# taad.net
KiCad netlist of a schematic drawn in EAGLE
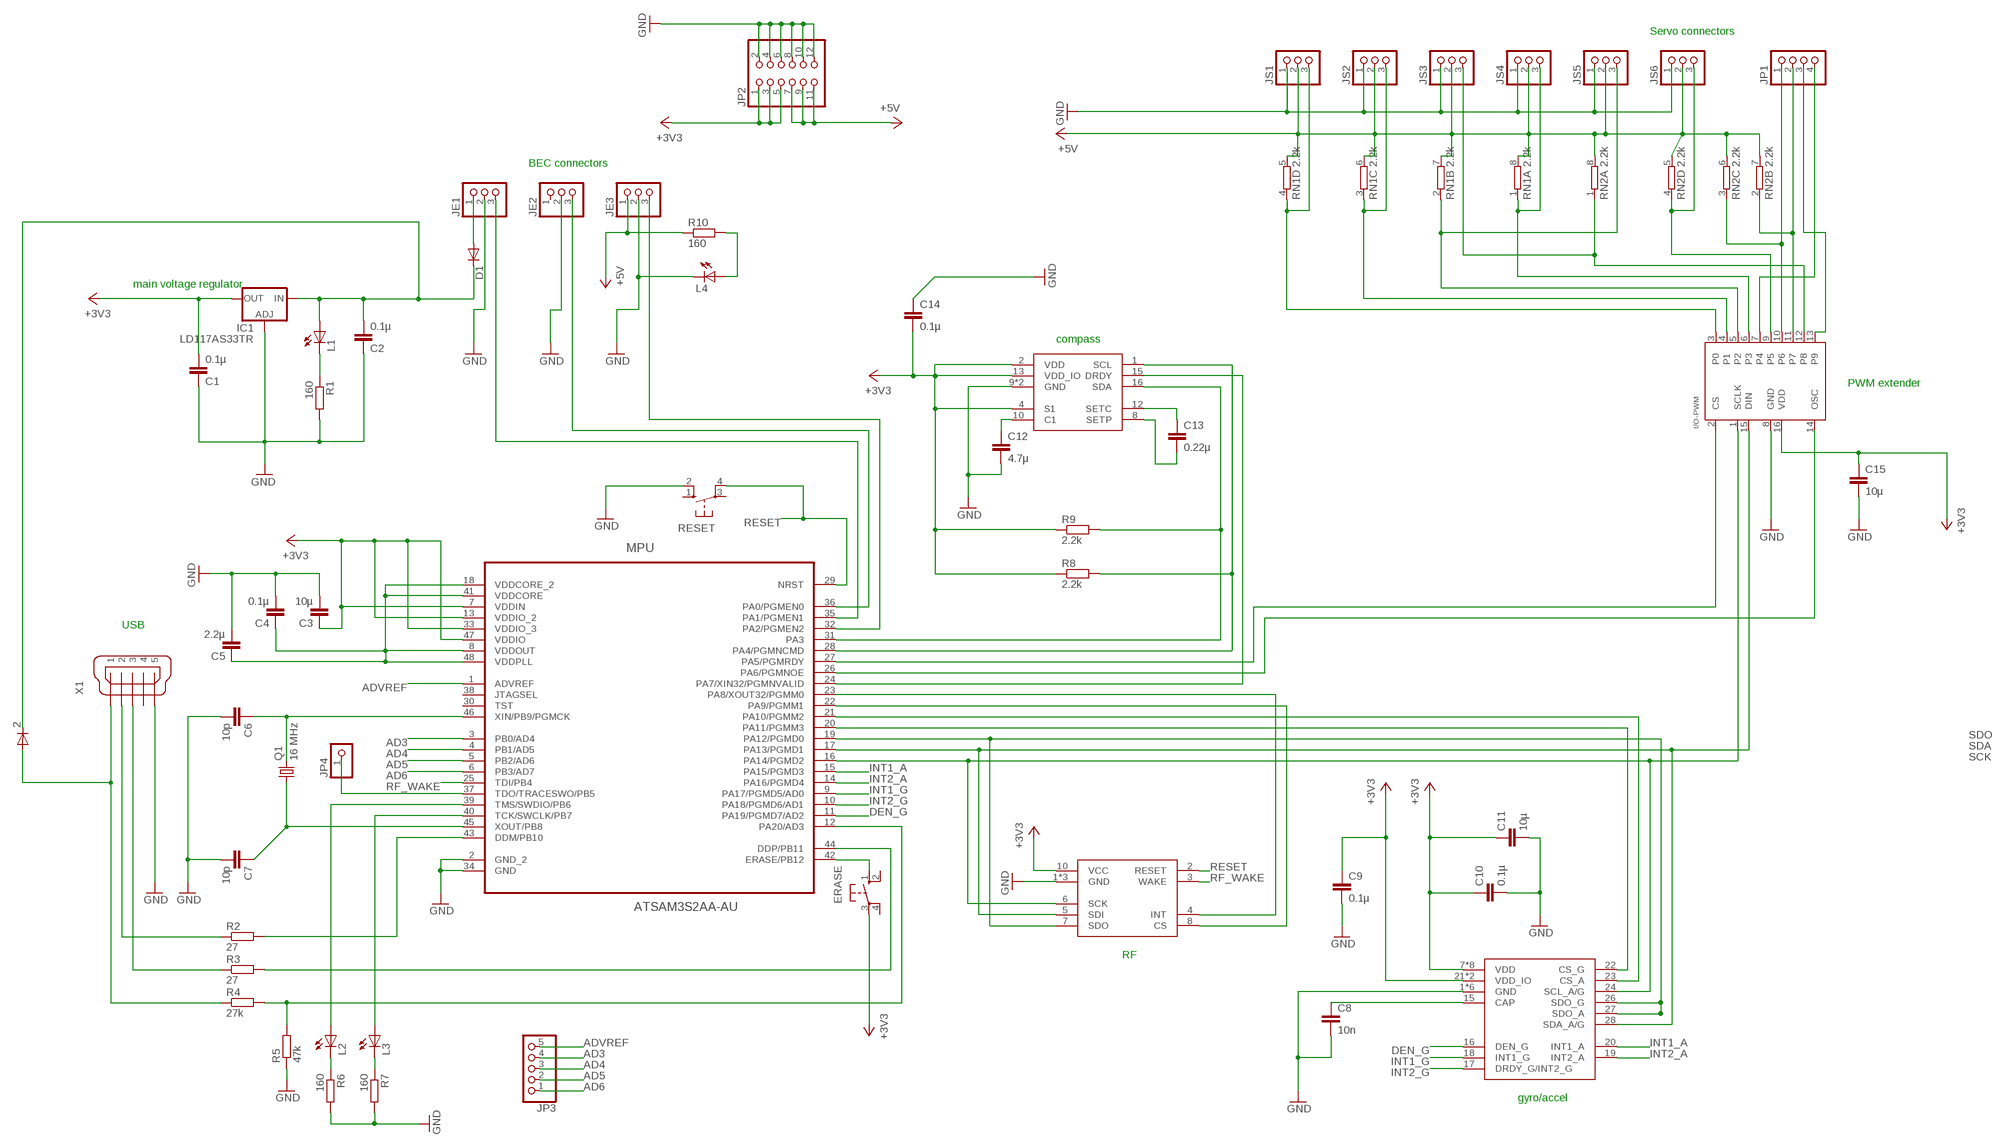
[diagram p0: schematic, sheet 1]

(export (version "E")
  (design (tool "Eeschema 10.0.6"))
  (components
    (comp (ref "2")
      (value "DIODE-SOD123")
      (footprint "eagle-import:SOD123")
      (libsource (lib "eagle-import") (part "DIODE-SOD123"))
    )
    (comp (ref "C1")
      (value "0.1µ")
      (footprint "eagle-import:C0805")
      (libsource (lib "eagle-import") (part "resistor_C-EUC0805"))
    )
    (comp (ref "C2")
      (value "0.1µ")
      (footprint "eagle-import:C0805")
      (libsource (lib "eagle-import") (part "resistor_C-EUC0805"))
    )
    (comp (ref "C3")
      (value "10µ")
      (footprint "eagle-import:C0805")
      (libsource (lib "eagle-import") (part "C-EUC0805"))
    )
    (comp (ref "C4")
      (value "0.1µ")
      (footprint "eagle-import:C0805")
      (libsource (lib "eagle-import") (part "C-EUC0805"))
    )
    (comp (ref "C5")
      (value "2.2µ")
      (footprint "eagle-import:C0805")
      (libsource (lib "eagle-import") (part "C-EUC0805"))
    )
    (comp (ref "C6")
      (value "10p")
      (footprint "eagle-import:C0805")
      (libsource (lib "eagle-import") (part "resistor_C-EUC0805"))
    )
    (comp (ref "C7")
      (value "10p")
      (footprint "eagle-import:C0805")
      (libsource (lib "eagle-import") (part "resistor_C-EUC0805"))
    )
    (comp (ref "C8")
      (value "10n")
      (footprint "eagle-import:C0805")
      (libsource (lib "eagle-import") (part "C-EUC0805"))
    )
    (comp (ref "C9")
      (value "0.1µ")
      (footprint "eagle-import:C0805")
      (libsource (lib "eagle-import") (part "C-EUC0805"))
    )
    (comp (ref "C10")
      (value "0.1µ")
      (footprint "eagle-import:C0805")
      (libsource (lib "eagle-import") (part "C-EUC0805"))
    )
    (comp (ref "C11")
      (value "10µ")
      (footprint "eagle-import:C0805")
      (libsource (lib "eagle-import") (part "C-EUC0805"))
    )
    (comp (ref "C12")
      (value "4.7µ")
      (footprint "eagle-import:C0805")
      (libsource (lib "eagle-import") (part "C-EUC0805"))
    )
    (comp (ref "C13")
      (value "0.22µ")
      (footprint "eagle-import:C0805")
      (libsource (lib "eagle-import") (part "C-EUC0805"))
    )
    (comp (ref "C14")
      (value "0.1µ")
      (footprint "eagle-import:C0805")
      (libsource (lib "eagle-import") (part "C-EUC0805"))
    )
    (comp (ref "C15")
      (value "10µ")
      (footprint "eagle-import:C0805")
      (libsource (lib "eagle-import") (part "C-EUC0805"))
    )
    (comp (ref "COMPASS")
      (value "HMC5883L")
      (footprint "eagle-import:LPCC16")
      (libsource (lib "eagle-import") (part "HMC5883L"))
    )
    (comp (ref "D1")
      (value "DIODE-SOD123")
      (footprint "eagle-import:SOD123")
      (libsource (lib "eagle-import") (part "DIODE-SOD123"))
    )
    (comp (ref "ERASE")
      (value "10-XX")
      (footprint "eagle-import:B3F-10XX")
      (fields (field (name "MPN") "B3F-1000"))
      (libsource (lib "eagle-import") (part "10-XX"))
    )
    (comp (ref "GYRO/ACCEL")
      (value "LSM330DLC")
      (footprint "eagle-import:LGA-28L")
      (libsource (lib "eagle-import") (part "LSM330DLC"))
    )
    (comp (ref "I/O-PWM")
      (value "MAX6967AEE")
      (footprint "eagle-import:QSOP16")
      (libsource (lib "eagle-import") (part "MAX6967AEE"))
    )
    (comp (ref "IC1")
      (value "LD117AS33TR")
      (footprint "eagle-import:SOT223")
      (libsource (lib "eagle-import") (part "LD117A?S33TR"))
    )
    (comp (ref "JE1")
      (value "PINHD-1X3")
      (footprint "eagle-import:1X03")
      (libsource (lib "eagle-import") (part "PINHD-1X3"))
    )
    (comp (ref "JE2")
      (value "PINHD-1X3")
      (footprint "eagle-import:1X03")
      (libsource (lib "eagle-import") (part "PINHD-1X3"))
    )
    (comp (ref "JE3")
      (value "PINHD-1X3")
      (footprint "eagle-import:1X03")
      (libsource (lib "eagle-import") (part "PINHD-1X3"))
    )
    (comp (ref "JP1")
      (value "PINHD-1X4")
      (footprint "eagle-import:1X04")
      (libsource (lib "eagle-import") (part "PINHD-1X4"))
    )
    (comp (ref "JP2")
      (value "PINHD-2X6")
      (footprint "eagle-import:2X06")
      (libsource (lib "eagle-import") (part "PINHD-2X6"))
    )
    (comp (ref "JP3")
      (value "PINHD-1X5")
      (footprint "eagle-import:1X05")
      (libsource (lib "eagle-import") (part "PINHD-1X5"))
    )
    (comp (ref "JP4")
      (value "PINHD-1X1")
      (footprint "eagle-import:1X01")
      (libsource (lib "eagle-import") (part "PINHD-1X1"))
    )
    (comp (ref "JS1")
      (value "PINHD-1X3")
      (footprint "eagle-import:1X03")
      (libsource (lib "eagle-import") (part "PINHD-1X3"))
    )
    (comp (ref "JS2")
      (value "PINHD-1X3")
      (footprint "eagle-import:1X03")
      (libsource (lib "eagle-import") (part "PINHD-1X3"))
    )
    (comp (ref "JS3")
      (value "PINHD-1X3")
      (footprint "eagle-import:1X03")
      (libsource (lib "eagle-import") (part "PINHD-1X3"))
    )
    (comp (ref "JS4")
      (value "PINHD-1X3")
      (footprint "eagle-import:1X03")
      (libsource (lib "eagle-import") (part "PINHD-1X3"))
    )
    (comp (ref "JS5")
      (value "PINHD-1X3")
      (footprint "eagle-import:1X03")
      (libsource (lib "eagle-import") (part "PINHD-1X3"))
    )
    (comp (ref "JS6")
      (value "PINHD-1X3")
      (footprint "eagle-import:1X03")
      (libsource (lib "eagle-import") (part "PINHD-1X3"))
    )
    (comp (ref "L1")
      (value "LEDCHIP-LED0805")
      (footprint "eagle-import:CHIP-LED0805")
      (libsource (lib "eagle-import") (part "LEDCHIP-LED0805"))
    )
    (comp (ref "L2")
      (value "LEDCHIP-LED0805")
      (footprint "eagle-import:CHIP-LED0805")
      (libsource (lib "eagle-import") (part "LEDCHIP-LED0805"))
    )
    (comp (ref "L3")
      (value "LEDCHIP-LED0805")
      (footprint "eagle-import:CHIP-LED0805")
      (libsource (lib "eagle-import") (part "LEDCHIP-LED0805"))
    )
    (comp (ref "L4")
      (value "LEDCHIP-LED0805")
      (footprint "eagle-import:CHIP-LED0805")
      (libsource (lib "eagle-import") (part "LEDCHIP-LED0805"))
    )
    (comp (ref "MPU")
      (value "ATSAM3S2AA-AU")
      (footprint "eagle-import:QFP50P900X900X160-48N")
      (libsource (lib "eagle-import") (part "ATSAM3S2AA-AU"))
    )
    (comp (ref "Q1")
      (value "16 MHz")
      (footprint "eagle-import:HC49UP")
      (fields (field (name "OC_FARNELL") "unknown"))
      (libsource (lib "eagle-import") (part "CRYSTALHC49UP"))
    )
    (comp (ref "R1")
      (value "160")
      (footprint "eagle-import:R0805")
      (libsource (lib "eagle-import") (part "R-EU_R0805"))
    )
    (comp (ref "R2")
      (value "27")
      (footprint "eagle-import:R0805")
      (libsource (lib "eagle-import") (part "R-EU_R0805"))
    )
    (comp (ref "R3")
      (value "27")
      (footprint "eagle-import:R0805")
      (libsource (lib "eagle-import") (part "R-EU_R0805"))
    )
    (comp (ref "R4")
      (value "27k")
      (footprint "eagle-import:R0805")
      (libsource (lib "eagle-import") (part "R-EU_R0805"))
    )
    (comp (ref "R5")
      (value "47k")
      (footprint "eagle-import:R0805")
      (libsource (lib "eagle-import") (part "R-EU_R0805"))
    )
    (comp (ref "R6")
      (value "160")
      (footprint "eagle-import:R0805")
      (libsource (lib "eagle-import") (part "R-EU_R0805"))
    )
    (comp (ref "R7")
      (value "160")
      (footprint "eagle-import:R0805")
      (libsource (lib "eagle-import") (part "R-EU_R0805"))
    )
    (comp (ref "R8")
      (value "2.2k")
      (footprint "eagle-import:R0805")
      (libsource (lib "eagle-import") (part "R-EU_R0805"))
    )
    (comp (ref "R9")
      (value "2.2k")
      (footprint "eagle-import:R0805")
      (libsource (lib "eagle-import") (part "R-EU_R0805"))
    )
    (comp (ref "R10")
      (value "160")
      (footprint "eagle-import:R0805")
      (libsource (lib "eagle-import") (part "R-EU_R0805"))
    )
    (comp (ref "RESET")
      (value "10-XX")
      (footprint "eagle-import:B3F-10XX")
      (fields (field (name "MPN") "B3F-1000"))
      (libsource (lib "eagle-import") (part "10-XX"))
    )
    (comp (ref "RF")
      (value "MRF24J40MA_TRANSEIVER_MODULE")
      (footprint "eagle-import:PIN_HEADERS")
      (libsource (lib "eagle-import") (part "MRF24J40MA_TRANSEIVER_MODULE"))
    )
    (comp (ref "RN1")
      (value "2.2k")
      (footprint "eagle-import:EXB38V")
      (libsource (lib "eagle-import") (part "4R-NEXB38V"))
    )
    (comp (ref "RN2")
      (value "2.2k")
      (footprint "eagle-import:EXB38V")
      (libsource (lib "eagle-import") (part "4R-NEXB38V"))
    )
    (comp (ref "X1")
      (value "MINI-USB-32005-201")
      (footprint "eagle-import:32005-201")
      (libsource (lib "eagle-import") (part "MINI-USB-32005-201"))
    )
  )
  (nets
    (net (code "1") (name "+3V3") (class "Default")
      (node (ref "C1") (pin "2") (pinfunction "2_2") (pintype "passive"))
      (node (ref "C10") (pin "1") (pinfunction "1_1") (pintype "passive"))
      (node (ref "C11") (pin "1") (pinfunction "1_1") (pintype "passive"))
      (node (ref "C14") (pin "2") (pinfunction "2_2") (pintype "passive"))
      (node (ref "C15") (pin "1") (pinfunction "1_1") (pintype "passive"))
      (node (ref "C3") (pin "1") (pinfunction "1_1") (pintype "passive"))
      (node (ref "C9") (pin "1") (pinfunction "1_1") (pintype "passive"))
      (node (ref "COMPASS") (pin "13") (pinfunction "VDD_IO_13") (pintype "power_in"))
      (node (ref "COMPASS") (pin "2") (pinfunction "VDD_2") (pintype "power_in"))
      (node (ref "COMPASS") (pin "4") (pinfunction "S1_4") (pintype "power_in"))
      (node (ref "ERASE") (pin "3") (pinfunction "P_3") (pintype "passive"))
      (node (ref "GYRO/ACCEL") (pin "10") (pinfunction "VDD_10") (pintype "power_in"))
      (node (ref "GYRO/ACCEL") (pin "11") (pinfunction "VDD_11") (pintype "power_in"))
      (node (ref "GYRO/ACCEL") (pin "12") (pinfunction "VDD_12") (pintype "power_in"))
      (node (ref "GYRO/ACCEL") (pin "13") (pinfunction "VDD_13") (pintype "power_in"))
      (node (ref "GYRO/ACCEL") (pin "14") (pinfunction "VDD_14") (pintype "power_in"))
      (node (ref "GYRO/ACCEL") (pin "21") (pinfunction "VDD_IO_21") (pintype "power_in"))
      (node (ref "GYRO/ACCEL") (pin "25") (pinfunction "VDD_IO_25") (pintype "power_in"))
      (node (ref "GYRO/ACCEL") (pin "7") (pinfunction "VDD_7") (pintype "power_in"))
      (node (ref "GYRO/ACCEL") (pin "8") (pinfunction "VDD_8") (pintype "power_in"))
      (node (ref "GYRO/ACCEL") (pin "9") (pinfunction "VDD_9") (pintype "power_in"))
      (node (ref "I/O-PWM") (pin "16") (pinfunction "VDD_16") (pintype "bidirectional"))
      (node (ref "IC1") (pin "4") (pinfunction "OUT_4") (pintype "passive"))
      (node (ref "JP2") (pin "1") (pinfunction "1_1") (pintype "passive"))
      (node (ref "JP2") (pin "3") (pinfunction "3_3") (pintype "passive"))
      (node (ref "JP2") (pin "5") (pinfunction "5_5") (pintype "passive"))
      (node (ref "MPU") (pin "13") (pinfunction "VDDIO_2_13") (pintype "power_in"))
      (node (ref "MPU") (pin "33") (pinfunction "VDDIO_3_33") (pintype "power_in"))
      (node (ref "MPU") (pin "47") (pinfunction "VDDIO_47") (pintype "power_in"))
      (node (ref "MPU") (pin "7") (pinfunction "VDDIN_7") (pintype "power_in"))
      (node (ref "R8") (pin "1") (pinfunction "1_1") (pintype "passive"))
      (node (ref "R9") (pin "1") (pinfunction "1_1") (pintype "passive"))
      (node (ref "RF") (pin "10") (pinfunction "VCC_10") (pintype "power_in"))
    )
    (net (code "2") (name "+5V") (class "Default")
      (node (ref "JE3") (pin "1") (pinfunction "1_1") (pintype "passive"))
      (node (ref "JP2") (pin "11") (pinfunction "11_11") (pintype "passive"))
      (node (ref "JP2") (pin "7") (pinfunction "7_7") (pintype "passive"))
      (node (ref "JP2") (pin "9") (pinfunction "9_9") (pintype "passive"))
      (node (ref "JS1") (pin "2") (pinfunction "2_2") (pintype "passive"))
      (node (ref "JS2") (pin "2") (pinfunction "2_2") (pintype "passive"))
      (node (ref "JS3") (pin "2") (pinfunction "2_2") (pintype "passive"))
      (node (ref "JS4") (pin "2") (pinfunction "2_2") (pintype "passive"))
      (node (ref "JS5") (pin "2") (pinfunction "2_2") (pintype "passive"))
      (node (ref "JS6") (pin "2") (pinfunction "2_2") (pintype "passive"))
      (node (ref "R10") (pin "1") (pinfunction "1_1") (pintype "passive"))
      (node (ref "RN1") (pin "5") (pinfunction "2_5") (pintype "passive"))
      (node (ref "RN1") (pin "6") (pinfunction "2_6") (pintype "passive"))
      (node (ref "RN1") (pin "7") (pinfunction "2_7") (pintype "passive"))
      (node (ref "RN1") (pin "8") (pinfunction "2_8") (pintype "passive"))
      (node (ref "RN2") (pin "5") (pinfunction "2_5") (pintype "passive"))
      (node (ref "RN2") (pin "6") (pinfunction "2_6") (pintype "passive"))
      (node (ref "RN2") (pin "7") (pinfunction "2_7") (pintype "passive"))
      (node (ref "RN2") (pin "8") (pinfunction "2_8") (pintype "passive"))
    )
    (net (code "3") (name "/AD3") (class "Default")
      (node (ref "JP3") (pin "4") (pinfunction "4_4") (pintype "passive"))
      (node (ref "MPU") (pin "3") (pinfunction "PB0/AD4_3") (pintype "bidirectional"))
    )
    (net (code "4") (name "/AD4") (class "Default")
      (node (ref "JP3") (pin "3") (pinfunction "3_3") (pintype "passive"))
      (node (ref "MPU") (pin "4") (pinfunction "PB1/AD5_4") (pintype "bidirectional"))
    )
    (net (code "5") (name "/AD5") (class "Default")
      (node (ref "JP3") (pin "2") (pinfunction "2_2") (pintype "passive"))
      (node (ref "MPU") (pin "5") (pinfunction "PB2/AD6_5") (pintype "bidirectional"))
    )
    (net (code "6") (name "/AD6") (class "Default")
      (node (ref "JP3") (pin "1") (pinfunction "1_1") (pintype "passive"))
      (node (ref "MPU") (pin "6") (pinfunction "PB3/AD7_6") (pintype "bidirectional"))
    )
    (net (code "7") (name "/ADVREF") (class "Default")
      (node (ref "JP3") (pin "5") (pinfunction "5_5") (pintype "passive"))
      (node (ref "MPU") (pin "1") (pinfunction "ADVREF_1") (pintype "input"))
    )
    (net (code "8") (name "/DEN_G") (class "Default")
      (node (ref "GYRO/ACCEL") (pin "16") (pinfunction "DEN_G_16") (pintype "input"))
      (node (ref "MPU") (pin "11") (pinfunction "PA19/PGMD7/AD2_11") (pintype "bidirectional"))
    )
    (net (code "9") (name "/INT1_A") (class "Default")
      (node (ref "GYRO/ACCEL") (pin "20") (pinfunction "INT1_A_20") (pintype "output"))
      (node (ref "MPU") (pin "15") (pinfunction "PA15/PGMD3_15") (pintype "bidirectional"))
    )
    (net (code "10") (name "/INT1_G") (class "Default")
      (node (ref "GYRO/ACCEL") (pin "18") (pinfunction "INT1_G_18") (pintype "output"))
      (node (ref "MPU") (pin "9") (pinfunction "PA17/PGMD5/AD0_9") (pintype "bidirectional"))
    )
    (net (code "11") (name "/INT2_A") (class "Default")
      (node (ref "GYRO/ACCEL") (pin "19") (pinfunction "INT2_A_19") (pintype "output"))
      (node (ref "MPU") (pin "14") (pinfunction "PA16/PGMD4_14") (pintype "bidirectional"))
    )
    (net (code "12") (name "/INT2_G") (class "Default")
      (node (ref "GYRO/ACCEL") (pin "17") (pinfunction "DRDY_G/INT2_G_17") (pintype "output"))
      (node (ref "MPU") (pin "10") (pinfunction "PA18/PGMD6/AD1_10") (pintype "bidirectional"))
    )
    (net (code "13") (name "/RESET") (class "Default")
      (node (ref "MPU") (pin "29") (pinfunction "NRST_29") (pintype "bidirectional"))
      (node (ref "RESET") (pin "4") (pinfunction "P1_4") (pintype "passive"))
      (node (ref "RF") (pin "2") (pinfunction "RESET_2") (pintype "input"))
    )
    (net (code "14") (name "/RF_WAKE") (class "Default")
      (node (ref "MPU") (pin "25") (pinfunction "TDI/PB4_25") (pintype "bidirectional"))
      (node (ref "RF") (pin "3") (pinfunction "WAKE_3") (pintype "input"))
    )
    (net (code "15") (name "/SCK") (class "Default")
      (node (ref "GYRO/ACCEL") (pin "24") (pinfunction "SCL_A/G_24") (pintype "input"))
      (node (ref "I/O-PWM") (pin "1") (pinfunction "SCLK_1") (pintype "input"))
      (node (ref "MPU") (pin "16") (pinfunction "PA14/PGMD2_16") (pintype "bidirectional"))
      (node (ref "RF") (pin "6") (pinfunction "SCK_6") (pintype "input"))
    )
    (net (code "16") (name "/SDA") (class "Default")
      (node (ref "GYRO/ACCEL") (pin "28") (pinfunction "SDA_A/G_28") (pintype "input"))
      (node (ref "I/O-PWM") (pin "15") (pinfunction "DIN_15") (pintype "input"))
      (node (ref "MPU") (pin "17") (pinfunction "PA13/PGMD1_17") (pintype "bidirectional"))
      (node (ref "RF") (pin "5") (pinfunction "SDI_5") (pintype "input"))
    )
    (net (code "17") (name "/SDO") (class "Default")
      (node (ref "GYRO/ACCEL") (pin "26") (pinfunction "SDO_G_26") (pintype "output"))
      (node (ref "GYRO/ACCEL") (pin "27") (pinfunction "SDO_A_27") (pintype "output"))
      (node (ref "MPU") (pin "19") (pinfunction "PA12/PGMD0_19") (pintype "bidirectional"))
      (node (ref "RF") (pin "7") (pinfunction "SDO_7") (pintype "output"))
    )
    (net (code "18") (name "GND") (class "Default")
      (node (ref "C1") (pin "1") (pinfunction "1_1") (pintype "passive"))
      (node (ref "C10") (pin "2") (pinfunction "2_2") (pintype "passive"))
      (node (ref "C11") (pin "2") (pinfunction "2_2") (pintype "passive"))
      (node (ref "C12") (pin "2") (pinfunction "2_2") (pintype "passive"))
      (node (ref "C14") (pin "1") (pinfunction "1_1") (pintype "passive"))
      (node (ref "C15") (pin "2") (pinfunction "2_2") (pintype "passive"))
      (node (ref "C2") (pin "1") (pinfunction "1_1") (pintype "passive"))
      (node (ref "C3") (pin "2") (pinfunction "2_2") (pintype "passive"))
      (node (ref "C4") (pin "2") (pinfunction "2_2") (pintype "passive"))
      (node (ref "C5") (pin "2") (pinfunction "2_2") (pintype "passive"))
      (node (ref "C6") (pin "2") (pinfunction "2_2") (pintype "passive"))
      (node (ref "C7") (pin "2") (pinfunction "2_2") (pintype "passive"))
      (node (ref "C8") (pin "2") (pinfunction "2_2") (pintype "passive"))
      (node (ref "C9") (pin "2") (pinfunction "2_2") (pintype "passive"))
      (node (ref "COMPASS") (pin "11") (pinfunction "GND_11") (pintype "bidirectional"))
      (node (ref "COMPASS") (pin "9") (pinfunction "GND_9") (pintype "bidirectional"))
      (node (ref "GYRO/ACCEL") (pin "1") (pinfunction "GND_1") (pintype "power_in"))
      (node (ref "GYRO/ACCEL") (pin "2") (pinfunction "GND_2") (pintype "power_in"))
      (node (ref "GYRO/ACCEL") (pin "3") (pinfunction "GND_3") (pintype "power_in"))
      (node (ref "GYRO/ACCEL") (pin "4") (pinfunction "GND_4") (pintype "power_in"))
      (node (ref "GYRO/ACCEL") (pin "5") (pinfunction "GND_5") (pintype "power_in"))
      (node (ref "GYRO/ACCEL") (pin "6") (pinfunction "GND_6") (pintype "power_in"))
      (node (ref "I/O-PWM") (pin "8") (pinfunction "GND_8") (pintype "bidirectional"))
      (node (ref "IC1") (pin "1") (pinfunction "ADJ_1") (pintype "input"))
      (node (ref "JE1") (pin "2") (pinfunction "2_2") (pintype "passive"))
      (node (ref "JE2") (pin "2") (pinfunction "2_2") (pintype "passive"))
      (node (ref "JE3") (pin "2") (pinfunction "2_2") (pintype "passive"))
      (node (ref "JP2") (pin "10") (pinfunction "10_10") (pintype "passive"))
      (node (ref "JP2") (pin "12") (pinfunction "12_12") (pintype "passive"))
      (node (ref "JP2") (pin "2") (pinfunction "2_2") (pintype "passive"))
      (node (ref "JP2") (pin "4") (pinfunction "4_4") (pintype "passive"))
      (node (ref "JP2") (pin "6") (pinfunction "6_6") (pintype "passive"))
      (node (ref "JP2") (pin "8") (pinfunction "8_8") (pintype "passive"))
      (node (ref "JS1") (pin "1") (pinfunction "1_1") (pintype "passive"))
      (node (ref "JS2") (pin "1") (pinfunction "1_1") (pintype "passive"))
      (node (ref "JS3") (pin "1") (pinfunction "1_1") (pintype "passive"))
      (node (ref "JS4") (pin "1") (pinfunction "1_1") (pintype "passive"))
      (node (ref "JS5") (pin "1") (pinfunction "1_1") (pintype "passive"))
      (node (ref "JS6") (pin "1") (pinfunction "1_1") (pintype "passive"))
      (node (ref "L4") (pin "C") (pinfunction "C_C") (pintype "passive"))
      (node (ref "MPU") (pin "2") (pinfunction "GND_2_2") (pintype "passive"))
      (node (ref "MPU") (pin "34") (pinfunction "GND_34") (pintype "passive"))
      (node (ref "R1") (pin "2") (pinfunction "2_2") (pintype "passive"))
      (node (ref "R5") (pin "1") (pinfunction "1_1") (pintype "passive"))
      (node (ref "R6") (pin "2") (pinfunction "2_2") (pintype "passive"))
      (node (ref "R7") (pin "2") (pinfunction "2_2") (pintype "passive"))
      (node (ref "RESET") (pin "2") (pinfunction "S1_2") (pintype "passive"))
      (node (ref "RF") (pin "1") (pinfunction "GND_1") (pintype "power_in"))
      (node (ref "RF") (pin "11") (pinfunction "GND_11") (pintype "power_in"))
      (node (ref "RF") (pin "12") (pinfunction "GND_12") (pintype "power_in"))
      (node (ref "X1") (pin "5") (pinfunction "5_5") (pintype "passive"))
    )
    (net (code "19") (name "Net-(2-PadA)") (class "Default")
      (node (ref "2") (pin "A") (pinfunction "A_A") (pintype "passive"))
      (node (ref "R4") (pin "1") (pinfunction "1_1") (pintype "passive"))
      (node (ref "X1") (pin "1") (pinfunction "1_1") (pintype "passive"))
    )
    (net (code "20") (name "Net-(COMPASS-C1)") (class "Default")
      (node (ref "C12") (pin "1") (pinfunction "1_1") (pintype "passive"))
      (node (ref "COMPASS") (pin "10") (pinfunction "C1_10") (pintype "passive"))
    )
    (net (code "21") (name "Net-(COMPASS-DRDY)") (class "Default")
      (node (ref "COMPASS") (pin "15") (pinfunction "DRDY_15") (pintype "input"))
      (node (ref "MPU") (pin "24") (pinfunction "PA7/XIN32/PGMNVALID_24") (pintype "bidirectional"))
    )
    (net (code "22") (name "Net-(COMPASS-SCL)") (class "Default")
      (node (ref "COMPASS") (pin "1") (pinfunction "SCL_1") (pintype "input"))
      (node (ref "MPU") (pin "28") (pinfunction "PA4/PGMNCMD_28") (pintype "bidirectional"))
      (node (ref "R8") (pin "2") (pinfunction "2_2") (pintype "passive"))
    )
    (net (code "23") (name "Net-(COMPASS-SDA)") (class "Default")
      (node (ref "COMPASS") (pin "16") (pinfunction "SDA_16") (pintype "input"))
      (node (ref "MPU") (pin "31") (pinfunction "PA3_31") (pintype "bidirectional"))
      (node (ref "R9") (pin "2") (pinfunction "2_2") (pintype "passive"))
    )
    (net (code "24") (name "Net-(COMPASS-SETC)") (class "Default")
      (node (ref "C13") (pin "1") (pinfunction "1_1") (pintype "passive"))
      (node (ref "COMPASS") (pin "12") (pinfunction "SETC_12") (pintype "passive"))
    )
    (net (code "25") (name "Net-(COMPASS-SETP)") (class "Default")
      (node (ref "C13") (pin "2") (pinfunction "2_2") (pintype "passive"))
      (node (ref "COMPASS") (pin "8") (pinfunction "SETP_8") (pintype "passive"))
    )
    (net (code "26") (name "Net-(D1-PadA)") (class "Default")
      (node (ref "D1") (pin "A") (pinfunction "A_A") (pintype "passive"))
      (node (ref "JE1") (pin "1") (pinfunction "1_1") (pintype "passive"))
    )
    (net (code "27") (name "Net-(ERASE-S)") (class "Default")
      (node (ref "ERASE") (pin "1") (pinfunction "S_1") (pintype "passive"))
      (node (ref "MPU") (pin "42") (pinfunction "ERASE/PB12_42") (pintype "bidirectional"))
    )
    (net (code "28") (name "Net-(GYRO/ACCEL-CAP)") (class "Default")
      (node (ref "C8") (pin "1") (pinfunction "1_1") (pintype "passive"))
      (node (ref "GYRO/ACCEL") (pin "15") (pinfunction "CAP_15") (pintype "passive"))
    )
    (net (code "29") (name "Net-(GYRO/ACCEL-CS_A)") (class "Default")
      (node (ref "GYRO/ACCEL") (pin "23") (pinfunction "CS_A_23") (pintype "input"))
      (node (ref "MPU") (pin "21") (pinfunction "PA10/PGMM2_21") (pintype "bidirectional"))
    )
    (net (code "30") (name "Net-(GYRO/ACCEL-CS_G)") (class "Default")
      (node (ref "GYRO/ACCEL") (pin "22") (pinfunction "CS_G_22") (pintype "input"))
      (node (ref "MPU") (pin "20") (pinfunction "PA11/PGMM3_20") (pintype "bidirectional"))
    )
    (net (code "31") (name "Net-(I/O-PWM-CS)") (class "Default")
      (node (ref "I/O-PWM") (pin "2") (pinfunction "CS_2") (pintype "input"))
      (node (ref "MPU") (pin "27") (pinfunction "PA5/PGMRDY_27") (pintype "bidirectional"))
    )
    (net (code "32") (name "Net-(I/O-PWM-OSC)") (class "Default")
      (node (ref "I/O-PWM") (pin "14") (pinfunction "OSC_14") (pintype "input"))
      (node (ref "MPU") (pin "26") (pinfunction "PA6/PGMNOE_26") (pintype "bidirectional"))
    )
    (net (code "33") (name "Net-(I/O-PWM-P0)") (class "Default")
      (node (ref "I/O-PWM") (pin "3") (pinfunction "P0_3") (pintype "output"))
      (node (ref "JS1") (pin "3") (pinfunction "3_3") (pintype "passive"))
      (node (ref "RN1") (pin "4") (pinfunction "1_4") (pintype "passive"))
    )
    (net (code "34") (name "Net-(I/O-PWM-P1)") (class "Default")
      (node (ref "I/O-PWM") (pin "4") (pinfunction "P1_4") (pintype "output"))
      (node (ref "JS2") (pin "3") (pinfunction "3_3") (pintype "passive"))
      (node (ref "RN1") (pin "3") (pinfunction "1_3") (pintype "passive"))
    )
    (net (code "35") (name "Net-(I/O-PWM-P2)") (class "Default")
      (node (ref "I/O-PWM") (pin "5") (pinfunction "P2_5") (pintype "output"))
      (node (ref "JS5") (pin "3") (pinfunction "3_3") (pintype "passive"))
      (node (ref "RN1") (pin "2") (pinfunction "1_2") (pintype "passive"))
    )
    (net (code "36") (name "Net-(I/O-PWM-P3)") (class "Default")
      (node (ref "I/O-PWM") (pin "6") (pinfunction "P3_6") (pintype "output"))
      (node (ref "JS4") (pin "3") (pinfunction "3_3") (pintype "passive"))
      (node (ref "RN1") (pin "1") (pinfunction "1_1") (pintype "passive"))
    )
    (net (code "37") (name "Net-(I/O-PWM-P4)") (class "Default")
      (node (ref "I/O-PWM") (pin "7") (pinfunction "P4_7") (pintype "output"))
      (node (ref "JP1") (pin "4") (pinfunction "4_4") (pintype "passive"))
    )
    (net (code "38") (name "Net-(I/O-PWM-P5)") (class "Default")
      (node (ref "I/O-PWM") (pin "9") (pinfunction "P5_9") (pintype "output"))
      (node (ref "JS6") (pin "3") (pinfunction "3_3") (pintype "passive"))
      (node (ref "RN2") (pin "4") (pinfunction "1_4") (pintype "passive"))
    )
    (net (code "39") (name "Net-(I/O-PWM-P6)") (class "Default")
      (node (ref "I/O-PWM") (pin "10") (pinfunction "P6_10") (pintype "output"))
      (node (ref "JP1") (pin "1") (pinfunction "1_1") (pintype "passive"))
      (node (ref "RN2") (pin "3") (pinfunction "1_3") (pintype "passive"))
    )
    (net (code "40") (name "Net-(I/O-PWM-P7)") (class "Default")
      (node (ref "I/O-PWM") (pin "11") (pinfunction "P7_11") (pintype "output"))
      (node (ref "JP1") (pin "2") (pinfunction "2_2") (pintype "passive"))
      (node (ref "RN2") (pin "2") (pinfunction "1_2") (pintype "passive"))
    )
    (net (code "41") (name "Net-(I/O-PWM-P8)") (class "Default")
      (node (ref "I/O-PWM") (pin "12") (pinfunction "P8_12") (pintype "output"))
      (node (ref "JS3") (pin "3") (pinfunction "3_3") (pintype "passive"))
      (node (ref "RN2") (pin "1") (pinfunction "1_1") (pintype "passive"))
    )
    (net (code "42") (name "Net-(I/O-PWM-P9)") (class "Default")
      (node (ref "I/O-PWM") (pin "13") (pinfunction "P9_13") (pintype "output"))
      (node (ref "JP1") (pin "3") (pinfunction "3_3") (pintype "passive"))
    )
    (net (code "43") (name "Net-(IC1-IN)") (class "Default")
      (node (ref "2") (pin "C") (pinfunction "C_C") (pintype "passive"))
      (node (ref "C2") (pin "2") (pinfunction "2_2") (pintype "passive"))
      (node (ref "D1") (pin "C") (pinfunction "C_C") (pintype "passive"))
      (node (ref "IC1") (pin "3") (pinfunction "IN_3") (pintype "input"))
      (node (ref "L1") (pin "A") (pinfunction "A_A") (pintype "passive"))
    )
    (net (code "44") (name "Net-(L1-PadC)") (class "Default")
      (node (ref "L1") (pin "C") (pinfunction "C_C") (pintype "passive"))
      (node (ref "R1") (pin "1") (pinfunction "1_1") (pintype "passive"))
    )
    (net (code "45") (name "Net-(L2-PadC)") (class "Default")
      (node (ref "L2") (pin "C") (pinfunction "C_C") (pintype "passive"))
      (node (ref "R6") (pin "1") (pinfunction "1_1") (pintype "passive"))
    )
    (net (code "46") (name "Net-(L3-PadC)") (class "Default")
      (node (ref "L3") (pin "C") (pinfunction "C_C") (pintype "passive"))
      (node (ref "R7") (pin "1") (pinfunction "1_1") (pintype "passive"))
    )
    (net (code "47") (name "Net-(L4-PadA)") (class "Default")
      (node (ref "L4") (pin "A") (pinfunction "A_A") (pintype "passive"))
      (node (ref "R10") (pin "2") (pinfunction "2_2") (pintype "passive"))
    )
    (net (code "48") (name "Net-(MPU-DDM{slash}PB10)") (class "Default")
      (node (ref "MPU") (pin "43") (pinfunction "DDM/PB10_43") (pintype "bidirectional"))
      (node (ref "R2") (pin "2") (pinfunction "2_2") (pintype "passive"))
    )
    (net (code "49") (name "Net-(MPU-DDP{slash}PB11)") (class "Default")
      (node (ref "MPU") (pin "44") (pinfunction "DDP/PB11_44") (pintype "bidirectional"))
      (node (ref "R3") (pin "2") (pinfunction "2_2") (pintype "passive"))
    )
    (net (code "50") (name "Net-(MPU-PA0{slash}PGMEN0)") (class "Default")
      (node (ref "JE2") (pin "3") (pinfunction "3_3") (pintype "passive"))
      (node (ref "MPU") (pin "36") (pinfunction "PA0/PGMEN0_36") (pintype "bidirectional"))
    )
    (net (code "51") (name "Net-(MPU-PA1{slash}PGMEN1)") (class "Default")
      (node (ref "JE1") (pin "3") (pinfunction "3_3") (pintype "passive"))
      (node (ref "MPU") (pin "35") (pinfunction "PA1/PGMEN1_35") (pintype "bidirectional"))
    )
    (net (code "52") (name "Net-(MPU-PA2{slash}PGMEN2)") (class "Default")
      (node (ref "JE3") (pin "3") (pinfunction "3_3") (pintype "passive"))
      (node (ref "MPU") (pin "32") (pinfunction "PA2/PGMEN2_32") (pintype "bidirectional"))
    )
    (net (code "53") (name "Net-(MPU-PA8{slash}XOUT32{slash}PGMM0)") (class "Default")
      (node (ref "MPU") (pin "23") (pinfunction "PA8/XOUT32/PGMM0_23") (pintype "bidirectional"))
      (node (ref "RF") (pin "4") (pinfunction "INT_4") (pintype "output"))
    )
    (net (code "54") (name "Net-(MPU-PA9{slash}PGMM1)") (class "Default")
      (node (ref "MPU") (pin "22") (pinfunction "PA9/PGMM1_22") (pintype "bidirectional"))
      (node (ref "RF") (pin "8") (pinfunction "CS_8") (pintype "input"))
    )
    (net (code "55") (name "Net-(MPU-PA20{slash}AD3)") (class "Default")
      (node (ref "MPU") (pin "12") (pinfunction "PA20/AD3_12") (pintype "bidirectional"))
      (node (ref "R4") (pin "2") (pinfunction "2_2") (pintype "passive"))
      (node (ref "R5") (pin "2") (pinfunction "2_2") (pintype "passive"))
    )
    (net (code "56") (name "Net-(MPU-TCK{slash}SWCLK{slash}PB7)") (class "Default")
      (node (ref "L3") (pin "A") (pinfunction "A_A") (pintype "passive"))
      (node (ref "MPU") (pin "40") (pinfunction "TCK/SWCLK/PB7_40") (pintype "bidirectional"))
    )
    (net (code "57") (name "Net-(MPU-TDO{slash}TRACESWO{slash}PB5)") (class "Default")
      (node (ref "JP4") (pin "1") (pinfunction "1_1") (pintype "passive"))
      (node (ref "MPU") (pin "37") (pinfunction "TDO/TRACESWO/PB5_37") (pintype "bidirectional"))
    )
    (net (code "58") (name "Net-(MPU-TMS{slash}SWDIO{slash}PB6)") (class "Default")
      (node (ref "L2") (pin "A") (pinfunction "A_A") (pintype "passive"))
      (node (ref "MPU") (pin "39") (pinfunction "TMS/SWDIO/PB6_39") (pintype "bidirectional"))
    )
    (net (code "59") (name "Net-(MPU-VDDCORE)") (class "Default")
      (node (ref "C4") (pin "1") (pinfunction "1_1") (pintype "passive"))
      (node (ref "C5") (pin "1") (pinfunction "1_1") (pintype "passive"))
      (node (ref "MPU") (pin "18") (pinfunction "VDDCORE_2_18") (pintype "power_in"))
      (node (ref "MPU") (pin "41") (pinfunction "VDDCORE_41") (pintype "power_in"))
      (node (ref "MPU") (pin "48") (pinfunction "VDDPLL_48") (pintype "power_in"))
      (node (ref "MPU") (pin "8") (pinfunction "VDDOUT_8") (pintype "power_in"))
    )
    (net (code "60") (name "Net-(MPU-XIN{slash}PB9{slash}PGMCK)") (class "Default")
      (node (ref "C6") (pin "1") (pinfunction "1_1") (pintype "passive"))
      (node (ref "MPU") (pin "46") (pinfunction "XIN/PB9/PGMCK_46") (pintype "input"))
      (node (ref "Q1") (pin "2") (pinfunction "2_2") (pintype "passive"))
    )
    (net (code "61") (name "Net-(MPU-XOUT{slash}PB8)") (class "Default")
      (node (ref "C7") (pin "1") (pinfunction "1_1") (pintype "passive"))
      (node (ref "MPU") (pin "45") (pinfunction "XOUT/PB8_45") (pintype "output"))
      (node (ref "Q1") (pin "1") (pinfunction "1_1") (pintype "passive"))
    )
    (net (code "62") (name "Net-(R2-Pad1)") (class "Default")
      (node (ref "R2") (pin "1") (pinfunction "1_1") (pintype "passive"))
      (node (ref "X1") (pin "2") (pinfunction "2_2") (pintype "passive"))
    )
    (net (code "63") (name "Net-(R3-Pad1)") (class "Default")
      (node (ref "R3") (pin "1") (pinfunction "1_1") (pintype "passive"))
      (node (ref "X1") (pin "3") (pinfunction "3_3") (pintype "passive"))
    )
    (net (code "64") (name "unconnected-(ERASE-P1-Pad4)") (class "Default")
      (node (ref "ERASE") (pin "4") (pinfunction "P1_4") (pintype "passive"))
    )
    (net (code "65") (name "unconnected-(ERASE-S1-Pad2)") (class "Default")
      (node (ref "ERASE") (pin "2") (pinfunction "S1_2") (pintype "passive"))
    )
    (net (code "66") (name "unconnected-(JE2-Pad1)") (class "Default")
      (node (ref "JE2") (pin "1") (pinfunction "1_1") (pintype "passive"))
    )
    (net (code "67") (name "unconnected-(MPU-JTAGSEL-Pad38)") (class "Default")
      (node (ref "MPU") (pin "38") (pinfunction "JTAGSEL_38") (pintype "input"))
    )
    (net (code "68") (name "unconnected-(MPU-TST-Pad30)") (class "Default")
      (node (ref "MPU") (pin "30") (pinfunction "TST_30") (pintype "input"))
    )
    (net (code "69") (name "unconnected-(RESET-P-Pad3)") (class "Default")
      (node (ref "RESET") (pin "3") (pinfunction "P_3") (pintype "passive"))
    )
    (net (code "70") (name "unconnected-(RESET-S-Pad1)") (class "Default")
      (node (ref "RESET") (pin "1") (pinfunction "S_1") (pintype "passive"))
    )
    (net (code "71") (name "unconnected-(X1-Pad4)") (class "Default")
      (node (ref "X1") (pin "4") (pinfunction "4_4") (pintype "passive"))
    )
  )
)
